# SparkFun_Wireless_JoyStick.net
KiCad netlist of a schematic drawn in EAGLE
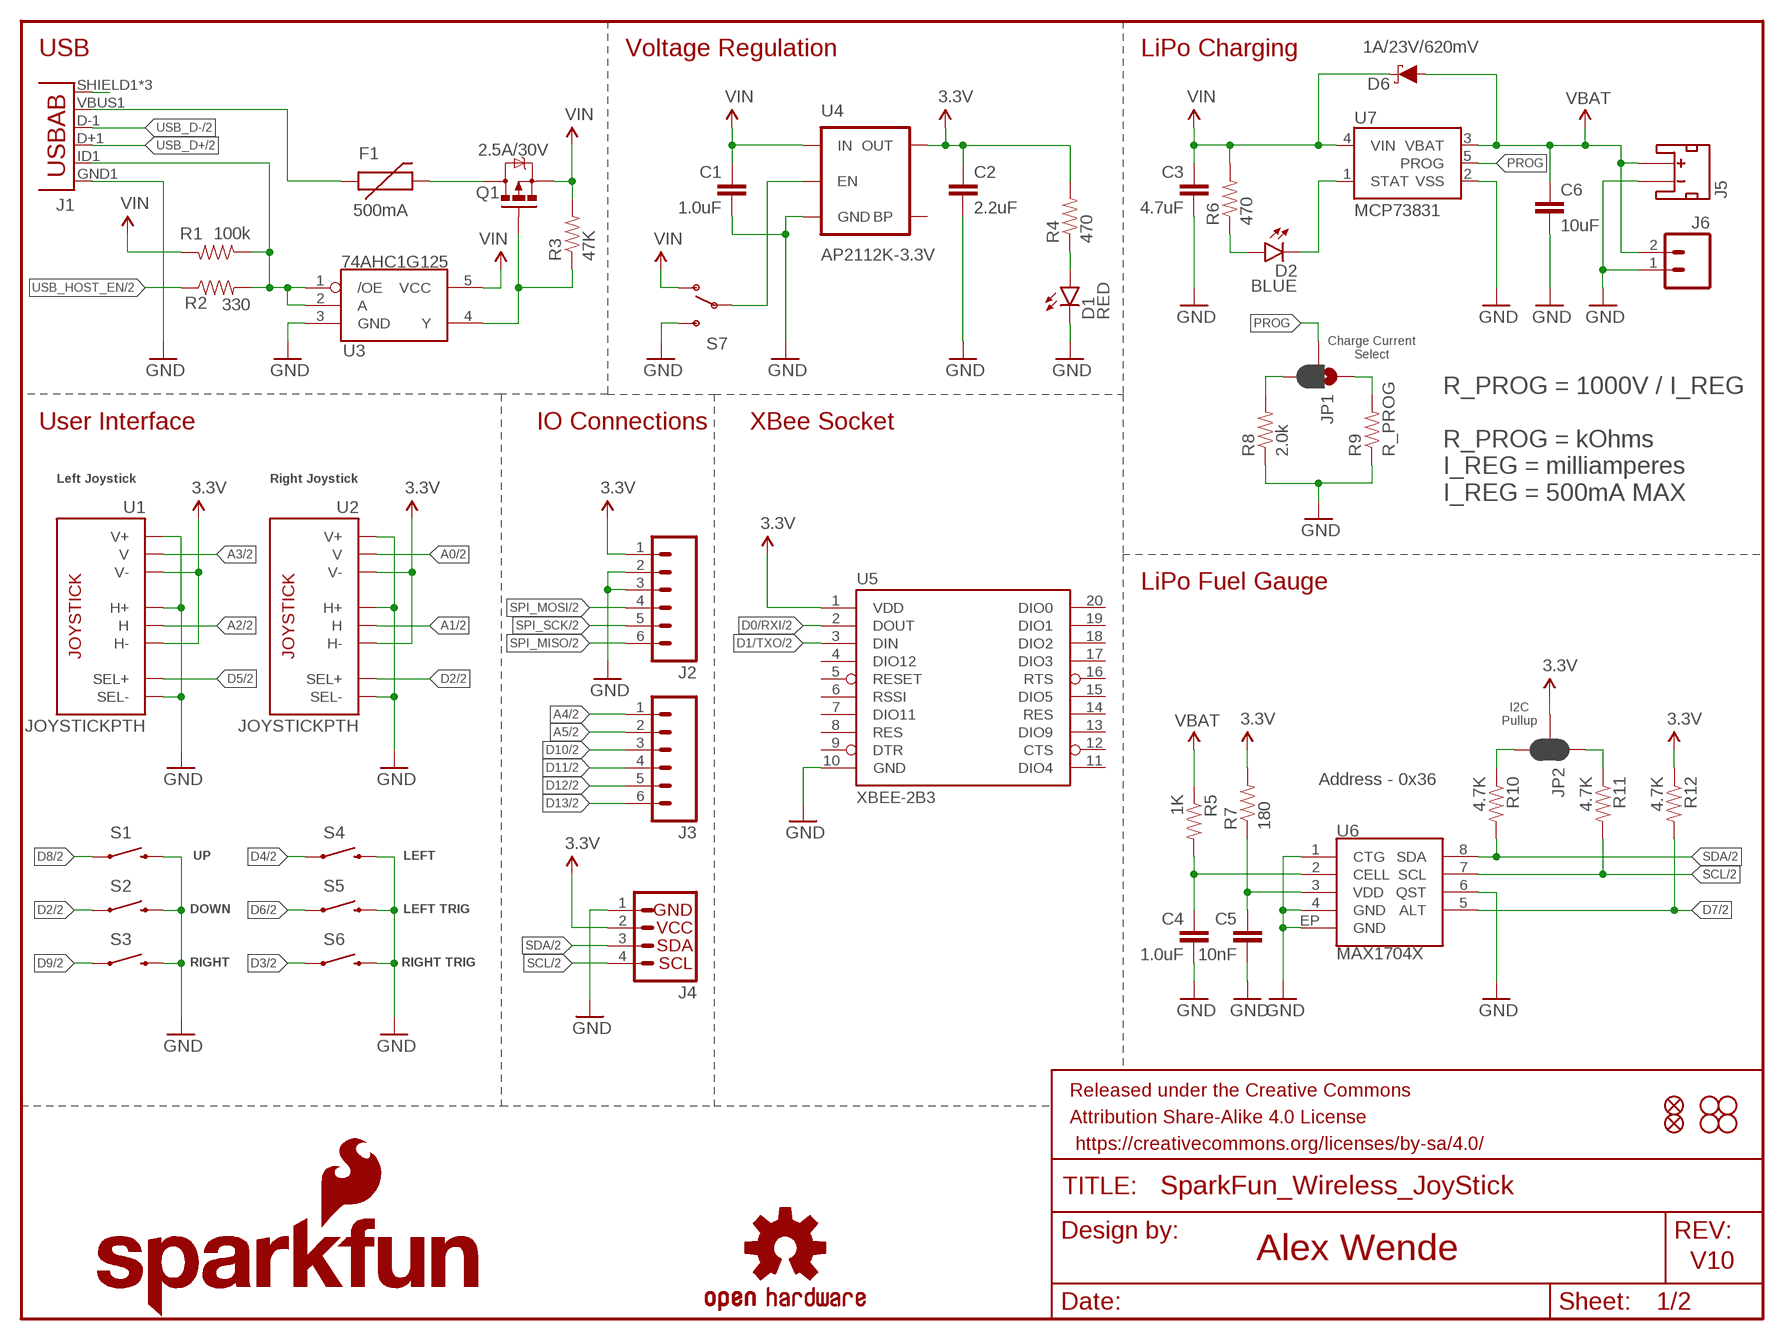
[diagram p0: schematic, sheet 1]
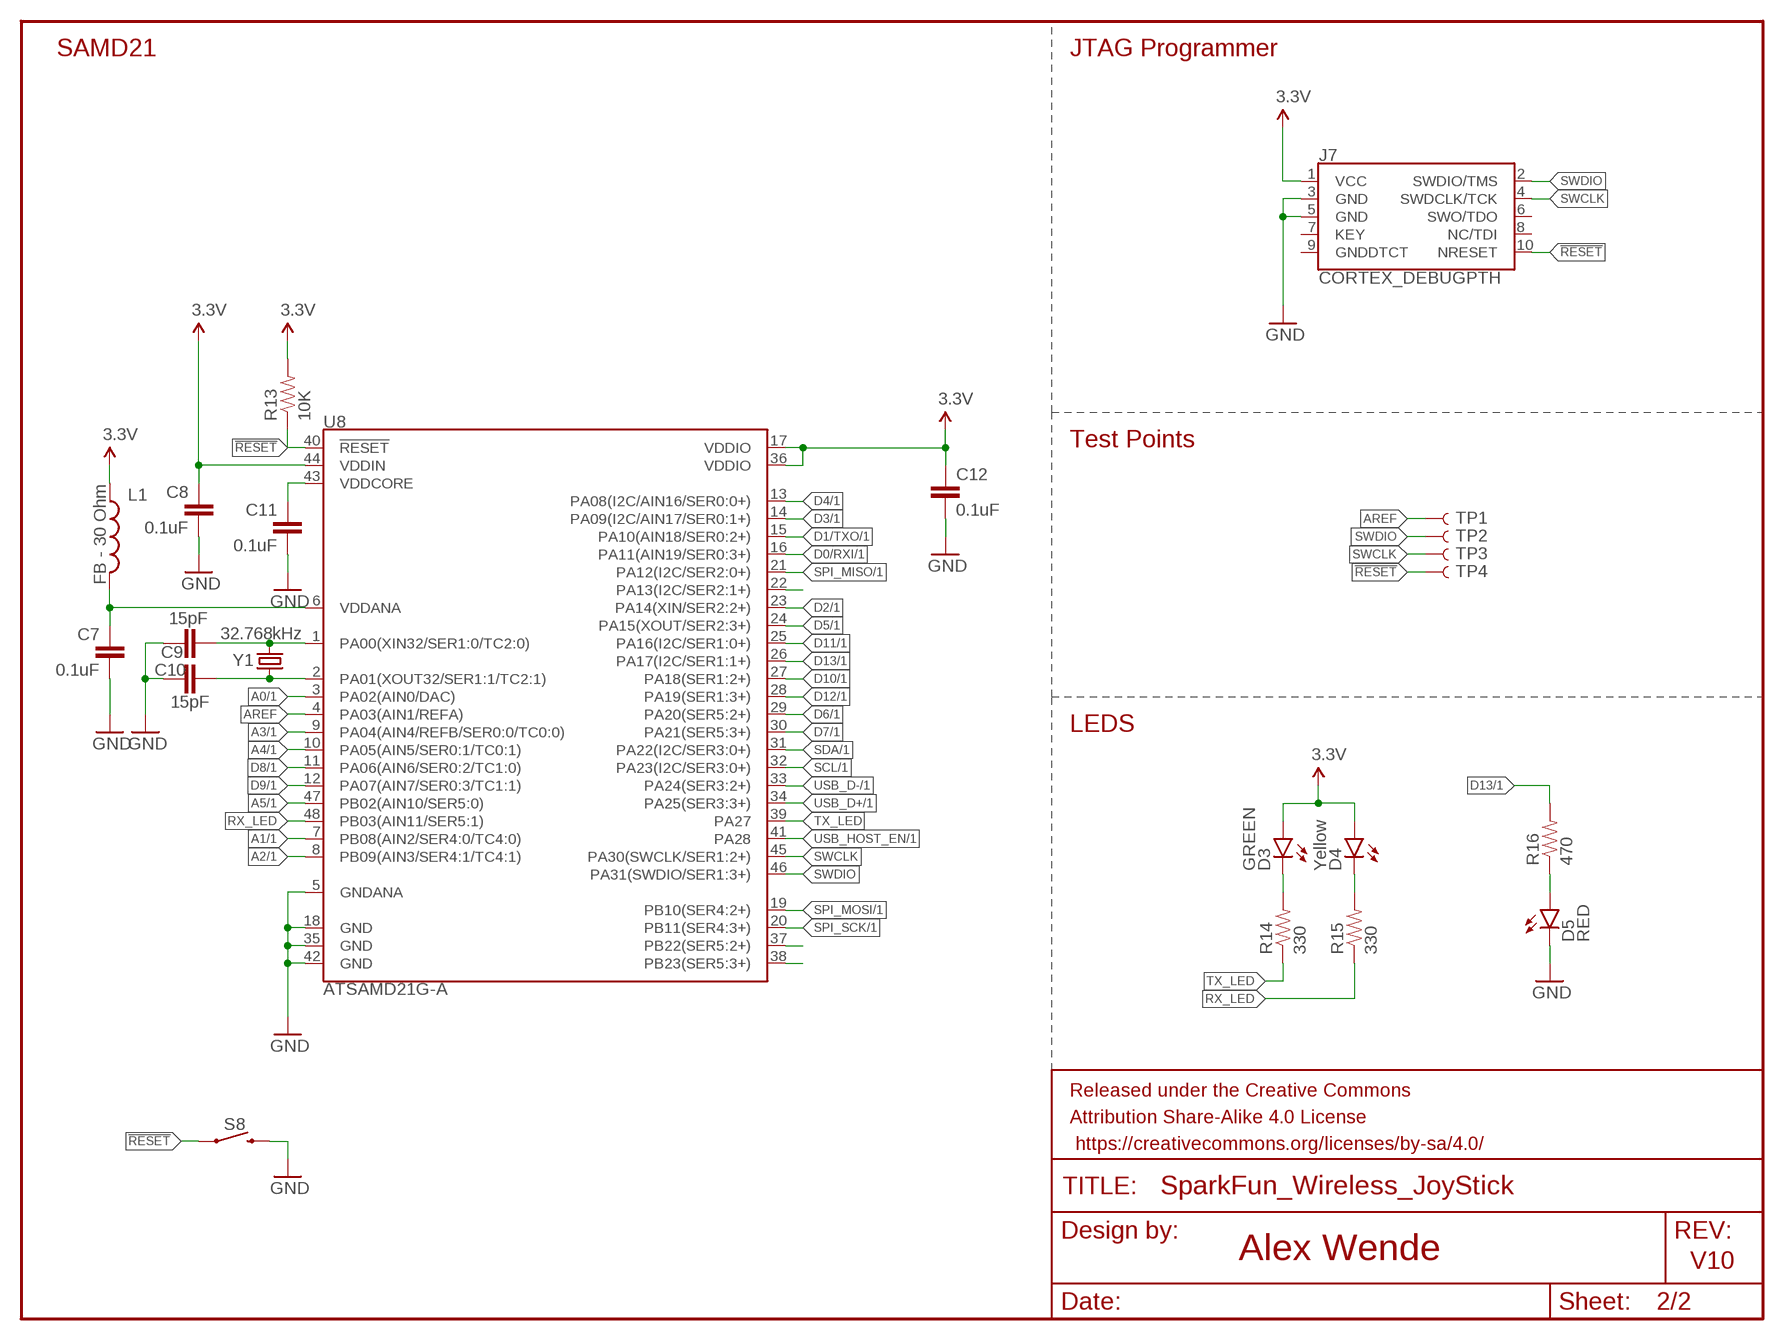
[diagram p1: schematic, sheet 2]

(export (version "E")
  (design (tool "Eeschema 10.0.6"))
  (components
    (comp (ref "C7")
      (value "0.1uF")
      (footprint "eagle-import:0603-CAP")
      (libsource (lib "eagle-import") (part "0.1UF-25V(+80/-20%)(0603)"))
    )
    (comp (ref "C8")
      (value "0.1uF")
      (footprint "eagle-import:0603-CAP")
      (libsource (lib "eagle-import") (part "0.1UF-25V(+80/-20%)(0603)"))
    )
    (comp (ref "C9")
      (value "15pF")
      (footprint "eagle-import:0603-CAP")
      (libsource (lib "eagle-import") (part "15PF-50V-5%(0603)"))
    )
    (comp (ref "C10")
      (value "15pF")
      (footprint "eagle-import:0603-CAP")
      (libsource (lib "eagle-import") (part "15PF-50V-5%(0603)"))
    )
    (comp (ref "C11")
      (value "0.1uF")
      (footprint "eagle-import:0603-CAP")
      (libsource (lib "eagle-import") (part "0.1UF-25V(+80/-20%)(0603)"))
    )
    (comp (ref "C12")
      (value "0.1uF")
      (footprint "eagle-import:0603-CAP")
      (libsource (lib "eagle-import") (part "0.1UF-25V(+80/-20%)(0603)"))
    )
    (comp (ref "D3")
      (value "GREEN")
      (footprint "eagle-import:LED-0603")
      (libsource (lib "eagle-import") (part "LED-GREEN0603"))
    )
    (comp (ref "D4")
      (value "Yellow")
      (footprint "eagle-import:LED-0603")
      (libsource (lib "eagle-import") (part "LED-YELLOW0603"))
    )
    (comp (ref "D5")
      (value "RED")
      (footprint "eagle-import:LED-0603")
      (libsource (lib "eagle-import") (part "LED-RED0603"))
    )
    (comp (ref "FRAME2")
      (value "FRAME-LETTERNO_PACKAGE")
      (footprint "eagle-import:DUMMY")
      (fields (field (name "DESIGNER") "Nobody"))
      (libsource (lib "eagle-import") (part "FRAME-LETTERNO_PACKAGE"))
    )
    (comp (ref "J7")
      (value "CORTEX_DEBUGPTH")
      (footprint "eagle-import:2X5-PTH-1.27MM")
      (libsource (lib "eagle-import") (part "CORTEX_DEBUGPTH"))
    )
    (comp (ref "L1")
      (value "FB - 30 Ohm")
      (footprint "eagle-import:0603")
      (fields (field (name "PROD_ID") "NDUC-07859"))
      (libsource (lib "eagle-import") (part "INDUCTOR30OHM,1.8A"))
    )
    (comp (ref "R13")
      (value "10K")
      (footprint "eagle-import:0603-RES")
      (libsource (lib "eagle-import") (part "10KOHM-1/10W-1%(0603)0603"))
    )
    (comp (ref "R14")
      (value "330")
      (footprint "eagle-import:0603-RES")
      (libsource (lib "eagle-import") (part "330OHM1/10W1%(0603)"))
    )
    (comp (ref "R15")
      (value "330")
      (footprint "eagle-import:0603-RES")
      (libsource (lib "eagle-import") (part "330OHM1/10W1%(0603)"))
    )
    (comp (ref "R16")
      (value "470")
      (footprint "eagle-import:0603-RES")
      (libsource (lib "eagle-import") (part "470OHM1/10W1%(0603)"))
    )
    (comp (ref "S8")
      (value "MOMENTARY-SWITCH-SPST-SMD-4.6X2.8MM")
      (footprint "eagle-import:TACTILE_SWITCH_SMD_4.6X2.8MM")
      (libsource (lib "eagle-import") (part "MOMENTARY-SWITCH-SPST-SMD-4.6X2.8MM"))
    )
    (comp (ref "TP1")
      (value "TEST-POINT3")
      (footprint "eagle-import:PAD.03X.03")
      (libsource (lib "eagle-import") (part "TEST-POINT3"))
    )
    (comp (ref "TP2")
      (value "TEST-POINT3")
      (footprint "eagle-import:PAD.03X.03")
      (libsource (lib "eagle-import") (part "TEST-POINT3"))
    )
    (comp (ref "TP3")
      (value "TEST-POINT3")
      (footprint "eagle-import:PAD.03X.03")
      (libsource (lib "eagle-import") (part "TEST-POINT3"))
    )
    (comp (ref "TP4")
      (value "TEST-POINT3")
      (footprint "eagle-import:PAD.03X.03")
      (libsource (lib "eagle-import") (part "TEST-POINT3"))
    )
    (comp (ref "U8")
      (value "ATSAMD21G-A")
      (footprint "eagle-import:TQFP-48")
      (libsource (lib "eagle-import") (part "ATSAMD21G-A"))
    )
    (comp (ref "Y1")
      (value "32.768kHz")
      (footprint "eagle-import:CRYSTAL-SMD-3.2X1.5MM")
      (libsource (lib "eagle-import") (part "CRYSTAL3.2X1.5MM"))
    )
    (comp (ref "C1")
      (value "1.0uF")
      (footprint "eagle-import:0805-CAP")
      (libsource (lib "eagle-import") (part "1.0UF-25V-+80/-20(0805){dblquote}"))
    )
    (comp (ref "C2")
      (value "2.2uF")
      (footprint "eagle-import:0603-CAP")
      (libsource (lib "eagle-import") (part "2.2UF-10V-20%(0603)"))
    )
    (comp (ref "C3")
      (value "4.7uF")
      (footprint "eagle-import:0603-CAP")
      (libsource (lib "eagle-import") (part "4.7UF-6.3V-10%(0603)0603"))
    )
    (comp (ref "C4")
      (value "1.0uF")
      (footprint "eagle-import:0603-CAP")
      (libsource (lib "eagle-import") (part "1.0UF-16V-10%(0603)"))
    )
    (comp (ref "C5")
      (value "10nF")
      (footprint "eagle-import:0603-CAP")
      (libsource (lib "eagle-import") (part "10NF/10000PF-50V-10%(0603)"))
    )
    (comp (ref "C6")
      (value "10uF")
      (footprint "eagle-import:0603-CAP")
      (libsource (lib "eagle-import") (part "10UF-6.3V-20%(0603)"))
    )
    (comp (ref "D1")
      (value "RED")
      (footprint "eagle-import:LED-0603")
      (libsource (lib "eagle-import") (part "LED-RED0603"))
    )
    (comp (ref "D2")
      (value "BLUE")
      (footprint "eagle-import:LED-0603")
      (libsource (lib "eagle-import") (part "LED-BLUE0603"))
    )
    (comp (ref "D6")
      (value "1A/23V/620mV")
      (footprint "eagle-import:SOD-323")
      (libsource (lib "eagle-import") (part "DIODE-SCHOTTKY-BAT20J"))
    )
    (comp (ref "F1")
      (value "500mA")
      (footprint "eagle-import:PTC-1206")
      (libsource (lib "eagle-import") (part "PTCSMD"))
    )
    (comp (ref "FD1")
      (value "FIDUCIALUFIDUCIAL")
      (footprint "eagle-import:MICRO-FIDUCIAL")
      (libsource (lib "eagle-import") (part "FIDUCIALUFIDUCIAL"))
    )
    (comp (ref "FD2")
      (value "FIDUCIALUFIDUCIAL")
      (footprint "eagle-import:MICRO-FIDUCIAL")
      (libsource (lib "eagle-import") (part "FIDUCIALUFIDUCIAL"))
    )
    (comp (ref "FRAME1")
      (value "FRAME-LETTER")
      (footprint "eagle-import:CREATIVE_COMMONS")
      (libsource (lib "eagle-import") (part "FRAME-LETTER"))
    )
    (comp (ref "H1")
      (value "STAND-OFF")
      (footprint "eagle-import:STAND-OFF")
      (libsource (lib "eagle-import") (part "STAND-OFF"))
    )
    (comp (ref "H2")
      (value "STAND-OFF")
      (footprint "eagle-import:STAND-OFF")
      (libsource (lib "eagle-import") (part "STAND-OFF"))
    )
    (comp (ref "H3")
      (value "STAND-OFF")
      (footprint "eagle-import:STAND-OFF")
      (libsource (lib "eagle-import") (part "STAND-OFF"))
    )
    (comp (ref "H4")
      (value "STAND-OFF")
      (footprint "eagle-import:STAND-OFF")
      (libsource (lib "eagle-import") (part "STAND-OFF"))
    )
    (comp (ref "J1")
      (value "USB-ABCONN-11794")
      (footprint "eagle-import:USB-AB-MICRO-SMD_V03")
      (libsource (lib "eagle-import") (part "USB-ABCONN-11794"))
    )
    (comp (ref "J2")
      (value "M06NO_SILK_FEMALE_PTH")
      (footprint "eagle-import:1X06_NO_SILK")
      (libsource (lib "eagle-import") (part "M06NO_SILK_FEMALE_PTH"))
    )
    (comp (ref "J3")
      (value "M06NO_SILK_FEMALE_PTH")
      (footprint "eagle-import:1X06_NO_SILK")
      (libsource (lib "eagle-import") (part "M06NO_SILK_FEMALE_PTH"))
    )
    (comp (ref "J4")
      (value "I2C_STANDARD_NO_SILK")
      (footprint "eagle-import:1X04_NO_SILK")
      (libsource (lib "eagle-import") (part "I2C_STANDARD_NO_SILK"))
    )
    (comp (ref "J5")
      (value "JST_2MM_MALE")
      (footprint "eagle-import:JST-2-SMD")
      (libsource (lib "eagle-import") (part "JST_2MM_MALE"))
    )
    (comp (ref "J6")
      (value "M021X02_NO_SILK")
      (footprint "eagle-import:1X02_NO_SILK")
      (libsource (lib "eagle-import") (part "M021X02_NO_SILK"))
    )
    (comp (ref "JP1")
      (value "JUMPER-PAD-3-2OF3_NC_BY_PASTE")
      (footprint "eagle-import:PAD-JUMPER-3-2OF3_NC_BY_PASTE_YES_SILK_FULL_BOX")
      (libsource (lib "eagle-import") (part "JUMPER-PAD-3-2OF3_NC_BY_PASTE"))
    )
    (comp (ref "JP2")
      (value "JUMPER-PAD-3-NC_BY_PASTE")
      (footprint "eagle-import:PAD-JUMPER-3-NC_BY_PASTE_YES_SILK_FULL_BOX")
      (libsource (lib "eagle-import") (part "JUMPER-PAD-3-NC_BY_PASTE"))
    )
    (comp (ref "LOGO1")
      (value "SFE_LOGO_NAME_FLAME.3_INCH")
      (footprint "eagle-import:SFE_LOGO_NAME_FLAME_.3")
      (libsource (lib "eagle-import") (part "SFE_LOGO_NAME_FLAME.3_INCH"))
    )
    (comp (ref "LOGO2")
      (value "OSHW-LOGOL")
      (footprint "eagle-import:OSHW-LOGO-L")
      (libsource (lib "eagle-import") (part "OSHW-LOGOL"))
    )
    (comp (ref "Q1")
      (value "2.5A/30V")
      (footprint "eagle-import:SOT23-3@1")
      (libsource (lib "eagle-import") (part "MOSFET-PCHANNELDMG2307L"))
    )
    (comp (ref "R1")
      (value "100k")
      (footprint "eagle-import:0603-RES")
      (libsource (lib "eagle-import") (part "100KOHM-1/10W-1%(0603)"))
    )
    (comp (ref "R2")
      (value "330")
      (footprint "eagle-import:0603-RES")
      (libsource (lib "eagle-import") (part "330OHM1/10W1%(0603)"))
    )
    (comp (ref "R3")
      (value "47K")
      (footprint "eagle-import:0603-RES")
      (libsource (lib "eagle-import") (part "47KOHM1/10W1%(0603)"))
    )
    (comp (ref "R4")
      (value "470")
      (footprint "eagle-import:0603-RES")
      (libsource (lib "eagle-import") (part "470OHM1/10W1%(0603)"))
    )
    (comp (ref "R5")
      (value "1K")
      (footprint "eagle-import:0603-RES")
      (libsource (lib "eagle-import") (part "1KOHM-1/10W-1%(0603)"))
    )
    (comp (ref "R6")
      (value "470")
      (footprint "eagle-import:0603-RES")
      (libsource (lib "eagle-import") (part "470OHM1/10W1%(0603)"))
    )
    (comp (ref "R7")
      (value "180")
      (footprint "eagle-import:0603-RES")
      (libsource (lib "eagle-import") (part "180OHM1/10W1%(0603)"))
    )
    (comp (ref "R8")
      (value "2.0k")
      (footprint "eagle-import:0603-RES")
      (libsource (lib "eagle-import") (part "2.0KOHM1/10W5%(0603)"))
    )
    (comp (ref "R9")
      (value "R_PROG")
      (footprint "eagle-import:AXIAL-0.4")
      (libsource (lib "eagle-import") (part "RESISTORPTH-1/4W"))
    )
    (comp (ref "R10")
      (value "4.7K")
      (footprint "eagle-import:0603-RES")
      (libsource (lib "eagle-import") (part "4.7KOHM-1/10W-1%(0603)"))
    )
    (comp (ref "R11")
      (value "4.7K")
      (footprint "eagle-import:0603-RES")
      (libsource (lib "eagle-import") (part "4.7KOHM-1/10W-1%(0603)"))
    )
    (comp (ref "R12")
      (value "4.7K")
      (footprint "eagle-import:0603-RES")
      (libsource (lib "eagle-import") (part "4.7KOHM-1/10W-1%(0603)"))
    )
    (comp (ref "S1")
      (value "SWITCH-MOMENTARY-212MM")
      (footprint "eagle-import:TACTILE-PTH-12MM")
      (libsource (lib "eagle-import") (part "SWITCH-MOMENTARY-212MM"))
    )
    (comp (ref "S2")
      (value "SWITCH-MOMENTARY-212MM")
      (footprint "eagle-import:TACTILE-PTH-12MM")
      (libsource (lib "eagle-import") (part "SWITCH-MOMENTARY-212MM"))
    )
    (comp (ref "S3")
      (value "SWITCH-MOMENTARY-212MM")
      (footprint "eagle-import:TACTILE-PTH-12MM")
      (libsource (lib "eagle-import") (part "SWITCH-MOMENTARY-212MM"))
    )
    (comp (ref "S4")
      (value "SWITCH-MOMENTARY-212MM")
      (footprint "eagle-import:TACTILE-PTH-12MM")
      (libsource (lib "eagle-import") (part "SWITCH-MOMENTARY-212MM"))
    )
    (comp (ref "S5")
      (value "SWITCH-MOMENTARY-2SIDE_EZ")
      (footprint "eagle-import:TACTILE-PTH-SIDEEZ")
      (libsource (lib "eagle-import") (part "SWITCH-MOMENTARY-2SIDE_EZ"))
    )
    (comp (ref "S6")
      (value "SWITCH-MOMENTARY-2SIDE_EZ")
      (footprint "eagle-import:TACTILE-PTH-SIDEEZ")
      (libsource (lib "eagle-import") (part "SWITCH-MOMENTARY-2SIDE_EZ"))
    )
    (comp (ref "S7")
      (value "SWITCH_SPDT")
      (footprint "eagle-import:KPS-1290")
      (libsource (lib "eagle-import") (part "SWITCH_SPDT"))
    )
    (comp (ref "U1")
      (value "JOYSTICKPTH")
      (footprint "eagle-import:JOYSTICK")
      (libsource (lib "eagle-import") (part "JOYSTICKPTH"))
    )
    (comp (ref "U2")
      (value "JOYSTICKPTH")
      (footprint "eagle-import:JOYSTICK")
      (libsource (lib "eagle-import") (part "JOYSTICKPTH"))
    )
    (comp (ref "U3")
      (value "74AHC1G125")
      (footprint "eagle-import:SOT23-5")
      (libsource (lib "eagle-import") (part "74AHC1G125"))
    )
    (comp (ref "U4")
      (value "AP2112K-3.3V")
      (footprint "eagle-import:SOT23-5")
      (libsource (lib "eagle-import") (part "V_REG_LDOSMD"))
    )
    (comp (ref "U5")
      (value "XBEE-2B3")
      (footprint "eagle-import:XBEE-SMD")
      (libsource (lib "eagle-import") (part "XBEE-2B3"))
    )
    (comp (ref "U6")
      (value "MAX1704X")
      (footprint "eagle-import:TDFN-8")
      (libsource (lib "eagle-import") (part "MAX1704X"))
    )
    (comp (ref "U7")
      (value "MCP73831")
      (footprint "eagle-import:SOT23-5")
      (libsource (lib "eagle-import") (part "MCP73831"))
    )
  )
  (nets
    (net (code "1") (name "3.3V") (class "Default")
      (node (ref "C12") (pin "1") (pinfunction "1_1") (pintype "passive"))
      (node (ref "C2") (pin "1") (pinfunction "1_1") (pintype "passive"))
      (node (ref "C8") (pin "1") (pinfunction "1_1") (pintype "passive"))
      (node (ref "D3") (pin "A") (pinfunction "A_A") (pintype "passive"))
      (node (ref "D4") (pin "A") (pinfunction "A_A") (pintype "passive"))
      (node (ref "J2") (pin "1") (pinfunction "1_1") (pintype "passive"))
      (node (ref "J4") (pin "2") (pinfunction "2_2") (pintype "passive"))
      (node (ref "J7") (pin "1") (pinfunction "VCC_1") (pintype "bidirectional"))
      (node (ref "JP2") (pin "2") (pinfunction "2_2") (pintype "passive"))
      (node (ref "L1") (pin "1") (pinfunction "1_1") (pintype "passive"))
      (node (ref "R12") (pin "1") (pinfunction "1_1") (pintype "passive"))
      (node (ref "R13") (pin "2") (pinfunction "2_2") (pintype "passive"))
      (node (ref "R4") (pin "2") (pinfunction "2_2") (pintype "passive"))
      (node (ref "R7") (pin "2") (pinfunction "2_2") (pintype "passive"))
      (node (ref "U1") (pin "H3") (pinfunction "H-_H3") (pintype "bidirectional"))
      (node (ref "U1") (pin "V3") (pinfunction "V-_V3") (pintype "bidirectional"))
      (node (ref "U2") (pin "H3") (pinfunction "H-_H3") (pintype "bidirectional"))
      (node (ref "U2") (pin "V3") (pinfunction "V-_V3") (pintype "bidirectional"))
      (node (ref "U4") (pin "5") (pinfunction "OUT_5") (pintype "passive"))
      (node (ref "U5") (pin "1") (pinfunction "VDD_1") (pintype "power_in"))
      (node (ref "U8") (pin "17") (pinfunction "VDDIO_17") (pintype "bidirectional"))
      (node (ref "U8") (pin "36") (pinfunction "VDDIO_36") (pintype "bidirectional"))
      (node (ref "U8") (pin "44") (pinfunction "VDDIN_44") (pintype "bidirectional"))
    )
    (net (code "2") (name "A0") (class "Default")
      (node (ref "U2") (pin "V2") (pinfunction "V_V2") (pintype "bidirectional"))
      (node (ref "U8") (pin "3") (pinfunction "PA02(AIN0/DAC)_3") (pintype "bidirectional"))
    )
    (net (code "3") (name "A1") (class "Default")
      (node (ref "U2") (pin "H2") (pinfunction "H_H2") (pintype "bidirectional"))
      (node (ref "U8") (pin "7") (pinfunction "PB08(AIN2/SER4:0/TC4:0)_7") (pintype "bidirectional"))
    )
    (net (code "4") (name "A2") (class "Default")
      (node (ref "U1") (pin "H2") (pinfunction "H_H2") (pintype "bidirectional"))
      (node (ref "U8") (pin "8") (pinfunction "PB09(AIN3/SER4:1/TC4:1)_8") (pintype "bidirectional"))
    )
    (net (code "5") (name "A3") (class "Default")
      (node (ref "U1") (pin "V2") (pinfunction "V_V2") (pintype "bidirectional"))
      (node (ref "U8") (pin "9") (pinfunction "PA04(AIN4/REFB/SER0:0/TC0:0)_9") (pintype "bidirectional"))
    )
    (net (code "6") (name "A4") (class "Default")
      (node (ref "J3") (pin "1") (pinfunction "1_1") (pintype "passive"))
      (node (ref "U8") (pin "10") (pinfunction "PA05(AIN5/SER0:1/TC0:1)_10") (pintype "bidirectional"))
    )
    (net (code "7") (name "A5") (class "Default")
      (node (ref "J3") (pin "2") (pinfunction "2_2") (pintype "passive"))
      (node (ref "U8") (pin "47") (pinfunction "PB02(AIN10/SER5:0)_47") (pintype "bidirectional"))
    )
    (net (code "8") (name "AREF") (class "Default")
      (node (ref "TP1") (pin "P$1") (pinfunction "1_P$1") (pintype "bidirectional"))
      (node (ref "U8") (pin "4") (pinfunction "PA03(AIN1/REFA)_4") (pintype "bidirectional"))
    )
    (net (code "9") (name "D0{slash}RXI") (class "Default")
      (node (ref "U5") (pin "2") (pinfunction "DOUT_2") (pintype "output"))
      (node (ref "U8") (pin "16") (pinfunction "PA11(AIN19/SER0:3+)_16") (pintype "bidirectional"))
    )
    (net (code "10") (name "D1{slash}TXO") (class "Default")
      (node (ref "U5") (pin "3") (pinfunction "DIN_3") (pintype "input"))
      (node (ref "U8") (pin "15") (pinfunction "PA10(AIN18/SER0:2+)_15") (pintype "bidirectional"))
    )
    (net (code "11") (name "D2") (class "Default")
      (node (ref "S2") (pin "1") (pinfunction "1_1") (pintype "passive"))
      (node (ref "U2") (pin "B1A") (pinfunction "SEL+_B1A") (pintype "bidirectional"))
      (node (ref "U8") (pin "23") (pinfunction "PA14(XIN/SER2:2+)_23") (pintype "bidirectional"))
    )
    (net (code "12") (name "D3") (class "Default")
      (node (ref "S6") (pin "1") (pinfunction "1_1") (pintype "passive"))
      (node (ref "U8") (pin "14") (pinfunction "PA09(I2C/AIN17/SER0:1+)_14") (pintype "bidirectional"))
    )
    (net (code "13") (name "D4") (class "Default")
      (node (ref "S4") (pin "1") (pinfunction "1_1") (pintype "passive"))
      (node (ref "U8") (pin "13") (pinfunction "PA08(I2C/AIN16/SER0:0+)_13") (pintype "bidirectional"))
    )
    (net (code "14") (name "D5") (class "Default")
      (node (ref "U1") (pin "B1A") (pinfunction "SEL+_B1A") (pintype "bidirectional"))
      (node (ref "U8") (pin "24") (pinfunction "PA15(XOUT/SER2:3+)_24") (pintype "bidirectional"))
    )
    (net (code "15") (name "D6") (class "Default")
      (node (ref "S5") (pin "1") (pinfunction "1_1") (pintype "passive"))
      (node (ref "U8") (pin "29") (pinfunction "PA20(SER5:2+)_29") (pintype "bidirectional"))
    )
    (net (code "16") (name "D7") (class "Default")
      (node (ref "R12") (pin "2") (pinfunction "2_2") (pintype "passive"))
      (node (ref "U6") (pin "5") (pinfunction "ALT_5") (pintype "bidirectional"))
      (node (ref "U8") (pin "30") (pinfunction "PA21(SER5:3+)_30") (pintype "bidirectional"))
    )
    (net (code "17") (name "D8") (class "Default")
      (node (ref "S1") (pin "1") (pinfunction "1_1") (pintype "passive"))
      (node (ref "U8") (pin "11") (pinfunction "PA06(AIN6/SER0:2/TC1:0)_11") (pintype "bidirectional"))
    )
    (net (code "18") (name "D9") (class "Default")
      (node (ref "S3") (pin "1") (pinfunction "1_1") (pintype "passive"))
      (node (ref "U8") (pin "12") (pinfunction "PA07(AIN7/SER0:3/TC1:1)_12") (pintype "bidirectional"))
    )
    (net (code "19") (name "D10") (class "Default")
      (node (ref "J3") (pin "3") (pinfunction "3_3") (pintype "passive"))
      (node (ref "U8") (pin "27") (pinfunction "PA18(SER1:2+)_27") (pintype "bidirectional"))
    )
    (net (code "20") (name "D11") (class "Default")
      (node (ref "J3") (pin "4") (pinfunction "4_4") (pintype "passive"))
      (node (ref "U8") (pin "25") (pinfunction "PA16(I2C/SER1:0+)_25") (pintype "bidirectional"))
    )
    (net (code "21") (name "D12") (class "Default")
      (node (ref "J3") (pin "5") (pinfunction "5_5") (pintype "passive"))
      (node (ref "U8") (pin "28") (pinfunction "PA19(SER1:3+)_28") (pintype "bidirectional"))
    )
    (net (code "22") (name "D13") (class "Default")
      (node (ref "J3") (pin "6") (pinfunction "6_6") (pintype "passive"))
      (node (ref "R16") (pin "2") (pinfunction "2_2") (pintype "passive"))
      (node (ref "U8") (pin "26") (pinfunction "PA17(I2C/SER1:1+)_26") (pintype "bidirectional"))
    )
    (net (code "23") (name "GND") (class "Default")
      (node (ref "C1") (pin "2") (pinfunction "2_2") (pintype "passive"))
      (node (ref "C10") (pin "1") (pinfunction "1_1") (pintype "passive"))
      (node (ref "C11") (pin "2") (pinfunction "2_2") (pintype "passive"))
      (node (ref "C12") (pin "2") (pinfunction "2_2") (pintype "passive"))
      (node (ref "C2") (pin "2") (pinfunction "2_2") (pintype "passive"))
      (node (ref "C3") (pin "2") (pinfunction "2_2") (pintype "passive"))
      (node (ref "C4") (pin "2") (pinfunction "2_2") (pintype "passive"))
      (node (ref "C5") (pin "2") (pinfunction "2_2") (pintype "passive"))
      (node (ref "C6") (pin "2") (pinfunction "2_2") (pintype "passive"))
      (node (ref "C7") (pin "2") (pinfunction "2_2") (pintype "passive"))
      (node (ref "C8") (pin "2") (pinfunction "2_2") (pintype "passive"))
      (node (ref "C9") (pin "1") (pinfunction "1_1") (pintype "passive"))
      (node (ref "D1") (pin "C") (pinfunction "C_C") (pintype "passive"))
      (node (ref "D5") (pin "C") (pinfunction "C_C") (pintype "passive"))
      (node (ref "J1") (pin "GND1") (pinfunction "GND_GND1") (pintype "bidirectional"))
      (node (ref "J2") (pin "2") (pinfunction "2_2") (pintype "passive"))
      (node (ref "J2") (pin "3") (pinfunction "3_3") (pintype "passive"))
      (node (ref "J4") (pin "1") (pinfunction "1_1") (pintype "passive"))
      (node (ref "J5") (pin "1") (pinfunction "-_1") (pintype "bidirectional"))
      (node (ref "J6") (pin "1") (pinfunction "1_1") (pintype "passive"))
      (node (ref "J7") (pin "3") (pinfunction "GND_3") (pintype "bidirectional"))
      (node (ref "J7") (pin "5") (pinfunction "GND_5") (pintype "bidirectional"))
      (node (ref "R8") (pin "1") (pinfunction "1_1") (pintype "passive"))
      (node (ref "R9") (pin "P$1") (pinfunction "1_P$1") (pintype "passive"))
      (node (ref "S1") (pin "3") (pinfunction "2_3") (pintype "passive"))
      (node (ref "S2") (pin "3") (pinfunction "2_3") (pintype "passive"))
      (node (ref "S3") (pin "3") (pinfunction "2_3") (pintype "passive"))
      (node (ref "S4") (pin "3") (pinfunction "2_3") (pintype "passive"))
      (node (ref "S5") (pin "2") (pinfunction "2_2") (pintype "passive"))
      (node (ref "S6") (pin "2") (pinfunction "2_2") (pintype "passive"))
      (node (ref "S7") (pin "S") (pinfunction "S_S") (pintype "passive"))
      (node (ref "S8") (pin "3") (pinfunction "2_3") (pintype "passive"))
      (node (ref "S8") (pin "4") (pinfunction "2_4") (pintype "passive"))
      (node (ref "U1") (pin "B2A") (pinfunction "SEL-_B2A") (pintype "bidirectional"))
      (node (ref "U1") (pin "H1") (pinfunction "H+_H1") (pintype "bidirectional"))
      (node (ref "U1") (pin "V1") (pinfunction "V+_V1") (pintype "bidirectional"))
      (node (ref "U2") (pin "B2A") (pinfunction "SEL-_B2A") (pintype "bidirectional"))
      (node (ref "U2") (pin "H1") (pinfunction "H+_H1") (pintype "bidirectional"))
      (node (ref "U2") (pin "V1") (pinfunction "V+_V1") (pintype "bidirectional"))
      (node (ref "U3") (pin "3") (pinfunction "GND_3") (pintype "bidirectional"))
      (node (ref "U4") (pin "2") (pinfunction "GND_2") (pintype "input"))
      (node (ref "U5") (pin "10") (pinfunction "GND_10") (pintype "power_in"))
      (node (ref "U6") (pin "1") (pinfunction "CTG_1") (pintype "bidirectional"))
      (node (ref "U6") (pin "4") (pinfunction "GND_4") (pintype "bidirectional"))
      (node (ref "U6") (pin "6") (pinfunction "QST_6") (pintype "bidirectional"))
      (node (ref "U6") (pin "EP") (pinfunction "GND_EP") (pintype "bidirectional"))
      (node (ref "U7") (pin "2") (pinfunction "VSS_2") (pintype "power_in"))
      (node (ref "U8") (pin "18") (pinfunction "GND_18") (pintype "bidirectional"))
      (node (ref "U8") (pin "35") (pinfunction "GND_35") (pintype "bidirectional"))
      (node (ref "U8") (pin "42") (pinfunction "GND_42") (pintype "bidirectional"))
      (node (ref "U8") (pin "5") (pinfunction "GNDANA_5") (pintype "bidirectional"))
    )
    (net (code "24") (name "Net-(D1-PadA)") (class "Default")
      (node (ref "D1") (pin "A") (pinfunction "A_A") (pintype "passive"))
      (node (ref "R4") (pin "1") (pinfunction "1_1") (pintype "passive"))
    )
    (net (code "25") (name "Net-(D2-PadA)") (class "Default")
      (node (ref "D2") (pin "A") (pinfunction "A_A") (pintype "passive"))
      (node (ref "R6") (pin "1") (pinfunction "1_1") (pintype "passive"))
    )
    (net (code "26") (name "Net-(D3-PadC)") (class "Default")
      (node (ref "D3") (pin "C") (pinfunction "C_C") (pintype "passive"))
      (node (ref "R14") (pin "2") (pinfunction "2_2") (pintype "passive"))
    )
    (net (code "27") (name "Net-(D4-PadC)") (class "Default")
      (node (ref "D4") (pin "C") (pinfunction "C_C") (pintype "passive"))
      (node (ref "R15") (pin "2") (pinfunction "2_2") (pintype "passive"))
    )
    (net (code "28") (name "Net-(D5-PadA)") (class "Default")
      (node (ref "D5") (pin "A") (pinfunction "A_A") (pintype "passive"))
      (node (ref "R16") (pin "1") (pinfunction "1_1") (pintype "passive"))
    )
    (net (code "29") (name "Net-(J1-SHIELD-PadSHIELD1)") (class "Default")
      (node (ref "J1") (pin "SHIELD1") (pinfunction "SHIELD_SHIELD1") (pintype "bidirectional"))
      (node (ref "J1") (pin "SHIELD2") (pinfunction "SHIELD_SHIELD2") (pintype "bidirectional"))
      (node (ref "J1") (pin "SHIELD3") (pinfunction "SHIELD_SHIELD3") (pintype "bidirectional"))
    )
    (net (code "30") (name "Net-(J1-USBID)") (class "Default")
      (node (ref "J1") (pin "ID1") (pinfunction "USBID_ID1") (pintype "bidirectional"))
      (node (ref "R1") (pin "1") (pinfunction "1_1") (pintype "passive"))
      (node (ref "R2") (pin "2") (pinfunction "2_2") (pintype "passive"))
      (node (ref "U3") (pin "1") (pinfunction "/OE_1") (pintype "bidirectional"))
      (node (ref "U3") (pin "2") (pinfunction "A_2") (pintype "bidirectional"))
    )
    (net (code "31") (name "Net-(J1-VBUS)") (class "Default")
      (node (ref "F1") (pin "1") (pinfunction "1_1") (pintype "bidirectional"))
      (node (ref "J1") (pin "VBUS1") (pinfunction "VBUS_VBUS1") (pintype "bidirectional"))
    )
    (net (code "32") (name "Net-(JP1-Pad3)") (class "Default")
      (node (ref "JP1") (pin "3") (pinfunction "3_3") (pintype "passive"))
      (node (ref "R8") (pin "2") (pinfunction "2_2") (pintype "passive"))
    )
    (net (code "33") (name "Net-(JP2-Pad1)") (class "Default")
      (node (ref "JP2") (pin "1") (pinfunction "1_1") (pintype "passive"))
      (node (ref "R11") (pin "1") (pinfunction "1_1") (pintype "passive"))
    )
    (net (code "34") (name "Net-(JP2-Pad3)") (class "Default")
      (node (ref "JP2") (pin "3") (pinfunction "3_3") (pintype "passive"))
      (node (ref "R10") (pin "1") (pinfunction "1_1") (pintype "passive"))
    )
    (net (code "35") (name "Net-(Q1-D)") (class "Default")
      (node (ref "F1") (pin "2") (pinfunction "2_2") (pintype "bidirectional"))
      (node (ref "Q1") (pin "3") (pinfunction "D_3") (pintype "passive"))
    )
    (net (code "36") (name "Net-(Q1-G)") (class "Default")
      (node (ref "Q1") (pin "1") (pinfunction "G_1") (pintype "passive"))
      (node (ref "R3") (pin "1") (pinfunction "1_1") (pintype "passive"))
      (node (ref "U3") (pin "4") (pinfunction "Y_4") (pintype "bidirectional"))
    )
    (net (code "37") (name "Net-(R9-2)") (class "Default")
      (node (ref "JP1") (pin "1") (pinfunction "1_1") (pintype "passive"))
      (node (ref "R9") (pin "P$2") (pinfunction "2_P$2") (pintype "passive"))
    )
    (net (code "38") (name "Net-(U4-EN)") (class "Default")
      (node (ref "S7") (pin "P") (pinfunction "P_P") (pintype "passive"))
      (node (ref "U4") (pin "3") (pinfunction "EN_3") (pintype "input"))
    )
    (net (code "39") (name "Net-(U6-CELL)") (class "Default")
      (node (ref "C4") (pin "1") (pinfunction "1_1") (pintype "passive"))
      (node (ref "R5") (pin "2") (pinfunction "2_2") (pintype "passive"))
      (node (ref "U6") (pin "2") (pinfunction "CELL_2") (pintype "bidirectional"))
    )
    (net (code "40") (name "Net-(U6-VDD)") (class "Default")
      (node (ref "C5") (pin "1") (pinfunction "1_1") (pintype "passive"))
      (node (ref "R7") (pin "1") (pinfunction "1_1") (pintype "passive"))
      (node (ref "U6") (pin "3") (pinfunction "VDD_3") (pintype "bidirectional"))
    )
    (net (code "41") (name "Net-(U7-STAT)") (class "Default")
      (node (ref "D2") (pin "C") (pinfunction "C_C") (pintype "passive"))
      (node (ref "U7") (pin "1") (pinfunction "STAT_1") (pintype "output"))
    )
    (net (code "42") (name "Net-(U8-PA00(XIN32{slash}SER1:0{slash}TC2:0))") (class "Default")
      (node (ref "C9") (pin "2") (pinfunction "2_2") (pintype "passive"))
      (node (ref "U8") (pin "1") (pinfunction "PA00(XIN32/SER1:0/TC2:0)_1") (pintype "bidirectional"))
      (node (ref "Y1") (pin "P$2") (pinfunction "2_P$2") (pintype "passive"))
    )
    (net (code "43") (name "Net-(U8-PA01(XOUT32{slash}SER1:1{slash}TC2:1))") (class "Default")
      (node (ref "C10") (pin "2") (pinfunction "2_2") (pintype "passive"))
      (node (ref "U8") (pin "2") (pinfunction "PA01(XOUT32/SER1:1/TC2:1)_2") (pintype "bidirectional"))
      (node (ref "Y1") (pin "P$1") (pinfunction "1_P$1") (pintype "passive"))
    )
    (net (code "44") (name "Net-(U8-VDDANA)") (class "Default")
      (node (ref "C7") (pin "1") (pinfunction "1_1") (pintype "passive"))
      (node (ref "L1") (pin "2") (pinfunction "2_2") (pintype "passive"))
      (node (ref "U8") (pin "6") (pinfunction "VDDANA_6") (pintype "bidirectional"))
    )
    (net (code "45") (name "Net-(U8-VDDCORE)") (class "Default")
      (node (ref "C11") (pin "1") (pinfunction "1_1") (pintype "passive"))
      (node (ref "U8") (pin "43") (pinfunction "VDDCORE_43") (pintype "bidirectional"))
    )
    (net (code "46") (name "PROG") (class "Default")
      (node (ref "JP1") (pin "2") (pinfunction "2_2") (pintype "passive"))
      (node (ref "U7") (pin "5") (pinfunction "PROG_5") (pintype "input"))
    )
    (net (code "47") (name "RX_LED") (class "Default")
      (node (ref "R15") (pin "1") (pinfunction "1_1") (pintype "passive"))
      (node (ref "U8") (pin "48") (pinfunction "PB03(AIN11/SER5:1)_48") (pintype "bidirectional"))
    )
    (net (code "48") (name "SCL") (class "Default")
      (node (ref "J4") (pin "4") (pinfunction "4_4") (pintype "passive"))
      (node (ref "R11") (pin "2") (pinfunction "2_2") (pintype "passive"))
      (node (ref "U6") (pin "7") (pinfunction "SCL_7") (pintype "bidirectional"))
      (node (ref "U8") (pin "32") (pinfunction "PA23(I2C/SER3:0+)_32") (pintype "bidirectional"))
    )
    (net (code "49") (name "SDA") (class "Default")
      (node (ref "J4") (pin "3") (pinfunction "3_3") (pintype "passive"))
      (node (ref "R10") (pin "2") (pinfunction "2_2") (pintype "passive"))
      (node (ref "U6") (pin "8") (pinfunction "SDA_8") (pintype "bidirectional"))
      (node (ref "U8") (pin "31") (pinfunction "PA22(I2C/SER3:0+)_31") (pintype "bidirectional"))
    )
    (net (code "50") (name "SPI_MISO") (class "Default")
      (node (ref "J2") (pin "6") (pinfunction "6_6") (pintype "passive"))
      (node (ref "U8") (pin "21") (pinfunction "PA12(I2C/SER2:0+)_21") (pintype "bidirectional"))
    )
    (net (code "51") (name "SPI_MOSI") (class "Default")
      (node (ref "J2") (pin "4") (pinfunction "4_4") (pintype "passive"))
      (node (ref "U8") (pin "19") (pinfunction "PB10(SER4:2+)_19") (pintype "bidirectional"))
    )
    (net (code "52") (name "SPI_SCK") (class "Default")
      (node (ref "J2") (pin "5") (pinfunction "5_5") (pintype "passive"))
      (node (ref "U8") (pin "20") (pinfunction "PB11(SER4:3+)_20") (pintype "bidirectional"))
    )
    (net (code "53") (name "SWCLK") (class "Default")
      (node (ref "J7") (pin "4") (pinfunction "SWDCLK/TCK_4") (pintype "bidirectional"))
      (node (ref "TP3") (pin "P$1") (pinfunction "1_P$1") (pintype "bidirectional"))
      (node (ref "U8") (pin "45") (pinfunction "PA30(SWCLK/SER1:2+)_45") (pintype "bidirectional"))
    )
    (net (code "54") (name "SWDIO") (class "Default")
      (node (ref "J7") (pin "2") (pinfunction "SWDIO/TMS_2") (pintype "bidirectional"))
      (node (ref "TP2") (pin "P$1") (pinfunction "1_P$1") (pintype "bidirectional"))
      (node (ref "U8") (pin "46") (pinfunction "PA31(SWDIO/SER1:3+)_46") (pintype "bidirectional"))
    )
    (net (code "55") (name "TX_LED") (class "Default")
      (node (ref "R14") (pin "1") (pinfunction "1_1") (pintype "passive"))
      (node (ref "U8") (pin "39") (pinfunction "PA27_39") (pintype "bidirectional"))
    )
    (net (code "56") (name "USB_D+") (class "Default")
      (node (ref "J1") (pin "D+1") (pinfunction "D+_D+1") (pintype "bidirectional"))
      (node (ref "U8") (pin "34") (pinfunction "PA25(SER3:3+)_34") (pintype "bidirectional"))
    )
    (net (code "57") (name "USB_D-") (class "Default")
      (node (ref "J1") (pin "D-1") (pinfunction "D-_D-1") (pintype "bidirectional"))
      (node (ref "U8") (pin "33") (pinfunction "PA24(SER3:2+)_33") (pintype "bidirectional"))
    )
    (net (code "58") (name "USB_HOST_EN") (class "Default")
      (node (ref "R2") (pin "1") (pinfunction "1_1") (pintype "passive"))
      (node (ref "U8") (pin "41") (pinfunction "PA28_41") (pintype "bidirectional"))
    )
    (net (code "59") (name "VBAT") (class "Default")
      (node (ref "C6") (pin "1") (pinfunction "1_1") (pintype "passive"))
      (node (ref "D6") (pin "A") (pinfunction "A_A") (pintype "passive"))
      (node (ref "J5") (pin "2") (pinfunction "+_2") (pintype "bidirectional"))
      (node (ref "J6") (pin "2") (pinfunction "2_2") (pintype "passive"))
      (node (ref "R5") (pin "1") (pinfunction "1_1") (pintype "passive"))
      (node (ref "U7") (pin "3") (pinfunction "VBAT_3") (pintype "power_in"))
    )
    (net (code "60") (name "VIN") (class "Default")
      (node (ref "C1") (pin "1") (pinfunction "1_1") (pintype "passive"))
      (node (ref "C3") (pin "1") (pinfunction "1_1") (pintype "passive"))
      (node (ref "D6") (pin "C") (pinfunction "C_C") (pintype "passive"))
      (node (ref "Q1") (pin "2") (pinfunction "S_2") (pintype "passive"))
      (node (ref "R1") (pin "2") (pinfunction "2_2") (pintype "passive"))
      (node (ref "R3") (pin "2") (pinfunction "2_2") (pintype "passive"))
      (node (ref "R6") (pin "2") (pinfunction "2_2") (pintype "passive"))
      (node (ref "S7") (pin "O") (pinfunction "O_O") (pintype "passive"))
      (node (ref "U3") (pin "5") (pinfunction "VCC_5") (pintype "bidirectional"))
      (node (ref "U4") (pin "1") (pinfunction "IN_1") (pintype "input"))
      (node (ref "U7") (pin "4") (pinfunction "VIN_4") (pintype "power_in"))
    )
    (net (code "61") (name "unconnected-(J5-PAD1-PadNC1)") (class "Default")
      (node (ref "J5") (pin "NC1") (pinfunction "PAD1_NC1") (pintype "bidirectional"))
    )
    (net (code "62") (name "unconnected-(J5-PAD2-PadNC2)") (class "Default")
      (node (ref "J5") (pin "NC2") (pinfunction "PAD2_NC2") (pintype "bidirectional"))
    )
    (net (code "63") (name "unconnected-(J7-GNDDTCT-Pad9)") (class "Default")
      (node (ref "J7") (pin "9") (pinfunction "GNDDTCT_9") (pintype "bidirectional"))
    )
    (net (code "64") (name "unconnected-(J7-KEY-Pad7)") (class "Default")
      (node (ref "J7") (pin "7") (pinfunction "KEY_7") (pintype "bidirectional"))
    )
    (net (code "65") (name "unconnected-(J7-NC{slash}TDI-Pad8)") (class "Default")
      (node (ref "J7") (pin "8") (pinfunction "NC/TDI_8") (pintype "bidirectional"))
    )
    (net (code "66") (name "unconnected-(J7-SWO{slash}TDO-Pad6)") (class "Default")
      (node (ref "J7") (pin "6") (pinfunction "SWO/TDO_6") (pintype "bidirectional"))
    )
    (net (code "67") (name "unconnected-(U4-BP-Pad4)") (class "Default")
      (node (ref "U4") (pin "4") (pinfunction "BP_4") (pintype "input"))
    )
    (net (code "68") (name "unconnected-(U5-CTS-Pad12)") (class "Default")
      (node (ref "U5") (pin "12") (pinfunction "CTS_12") (pintype "output"))
    )
    (net (code "69") (name "unconnected-(U5-DIO0-Pad20)") (class "Default")
      (node (ref "U5") (pin "20") (pinfunction "DIO0_20") (pintype "bidirectional"))
    )
    (net (code "70") (name "unconnected-(U5-DIO1-Pad19)") (class "Default")
      (node (ref "U5") (pin "19") (pinfunction "DIO1_19") (pintype "bidirectional"))
    )
    (net (code "71") (name "unconnected-(U5-DIO2-Pad18)") (class "Default")
      (node (ref "U5") (pin "18") (pinfunction "DIO2_18") (pintype "bidirectional"))
    )
    (net (code "72") (name "unconnected-(U5-DIO3-Pad17)") (class "Default")
      (node (ref "U5") (pin "17") (pinfunction "DIO3_17") (pintype "bidirectional"))
    )
    (net (code "73") (name "unconnected-(U5-DIO4-Pad11)") (class "Default")
      (node (ref "U5") (pin "11") (pinfunction "DIO4_11") (pintype "bidirectional"))
    )
    (net (code "74") (name "unconnected-(U5-DIO5-Pad15)") (class "Default")
      (node (ref "U5") (pin "15") (pinfunction "DIO5_15") (pintype "bidirectional"))
    )
    (net (code "75") (name "unconnected-(U5-DIO9-Pad13)") (class "Default")
      (node (ref "U5") (pin "13") (pinfunction "DIO9_13") (pintype "bidirectional"))
    )
    (net (code "76") (name "unconnected-(U5-DIO11-Pad7)") (class "Default")
      (node (ref "U5") (pin "7") (pinfunction "DIO11_7") (pintype "bidirectional"))
    )
    (net (code "77") (name "unconnected-(U5-DIO12-Pad4)") (class "Default")
      (node (ref "U5") (pin "4") (pinfunction "DIO12_4") (pintype "bidirectional"))
    )
    (net (code "78") (name "unconnected-(U5-DTR-Pad9)") (class "Default")
      (node (ref "U5") (pin "9") (pinfunction "DTR_9") (pintype "bidirectional"))
    )
    (net (code "79") (name "unconnected-(U5-RES-Pad8)") (class "Default")
      (node (ref "U5") (pin "8") (pinfunction "RES_8") (pintype "bidirectional"))
    )
    (net (code "80") (name "unconnected-(U5-RES-Pad14)") (class "Default")
      (node (ref "U5") (pin "14") (pinfunction "RES_14") (pintype "bidirectional"))
    )
    (net (code "81") (name "unconnected-(U5-RESET-Pad5)") (class "Default")
      (node (ref "U5") (pin "5") (pinfunction "RESET_5") (pintype "input"))
    )
    (net (code "82") (name "unconnected-(U5-RSSI-Pad6)") (class "Default")
      (node (ref "U5") (pin "6") (pinfunction "RSSI_6") (pintype "bidirectional"))
    )
    (net (code "83") (name "unconnected-(U5-RTS-Pad16)") (class "Default")
      (node (ref "U5") (pin "16") (pinfunction "RTS_16") (pintype "input"))
    )
    (net (code "84") (name "unconnected-(U8-PA13(I2C{slash}SER2:1+)-Pad22)") (class "Default")
      (node (ref "U8") (pin "22") (pinfunction "PA13(I2C/SER2:1+)_22") (pintype "bidirectional"))
    )
    (net (code "85") (name "unconnected-(U8-PB22(SER5:2+)-Pad37)") (class "Default")
      (node (ref "U8") (pin "37") (pinfunction "PB22(SER5:2+)_37") (pintype "bidirectional"))
    )
    (net (code "86") (name "unconnected-(U8-PB23(SER5:3+)-Pad38)") (class "Default")
      (node (ref "U8") (pin "38") (pinfunction "PB23(SER5:3+)_38") (pintype "bidirectional"))
    )
    (net (code "87") (name "~{RESET}") (class "Default")
      (node (ref "J7") (pin "10") (pinfunction "NRESET_10") (pintype "bidirectional"))
      (node (ref "R13") (pin "1") (pinfunction "1_1") (pintype "passive"))
      (node (ref "S8") (pin "1") (pinfunction "1_1") (pintype "passive"))
      (node (ref "S8") (pin "2") (pinfunction "1_2") (pintype "passive"))
      (node (ref "TP4") (pin "P$1") (pinfunction "1_P$1") (pintype "bidirectional"))
      (node (ref "U8") (pin "40") (pinfunction "~{RESET}_40") (pintype "bidirectional"))
    )
  )
)
